# 150225_AriloRX_REV2_0_0.net
KiCad netlist of a schematic drawn in EAGLE
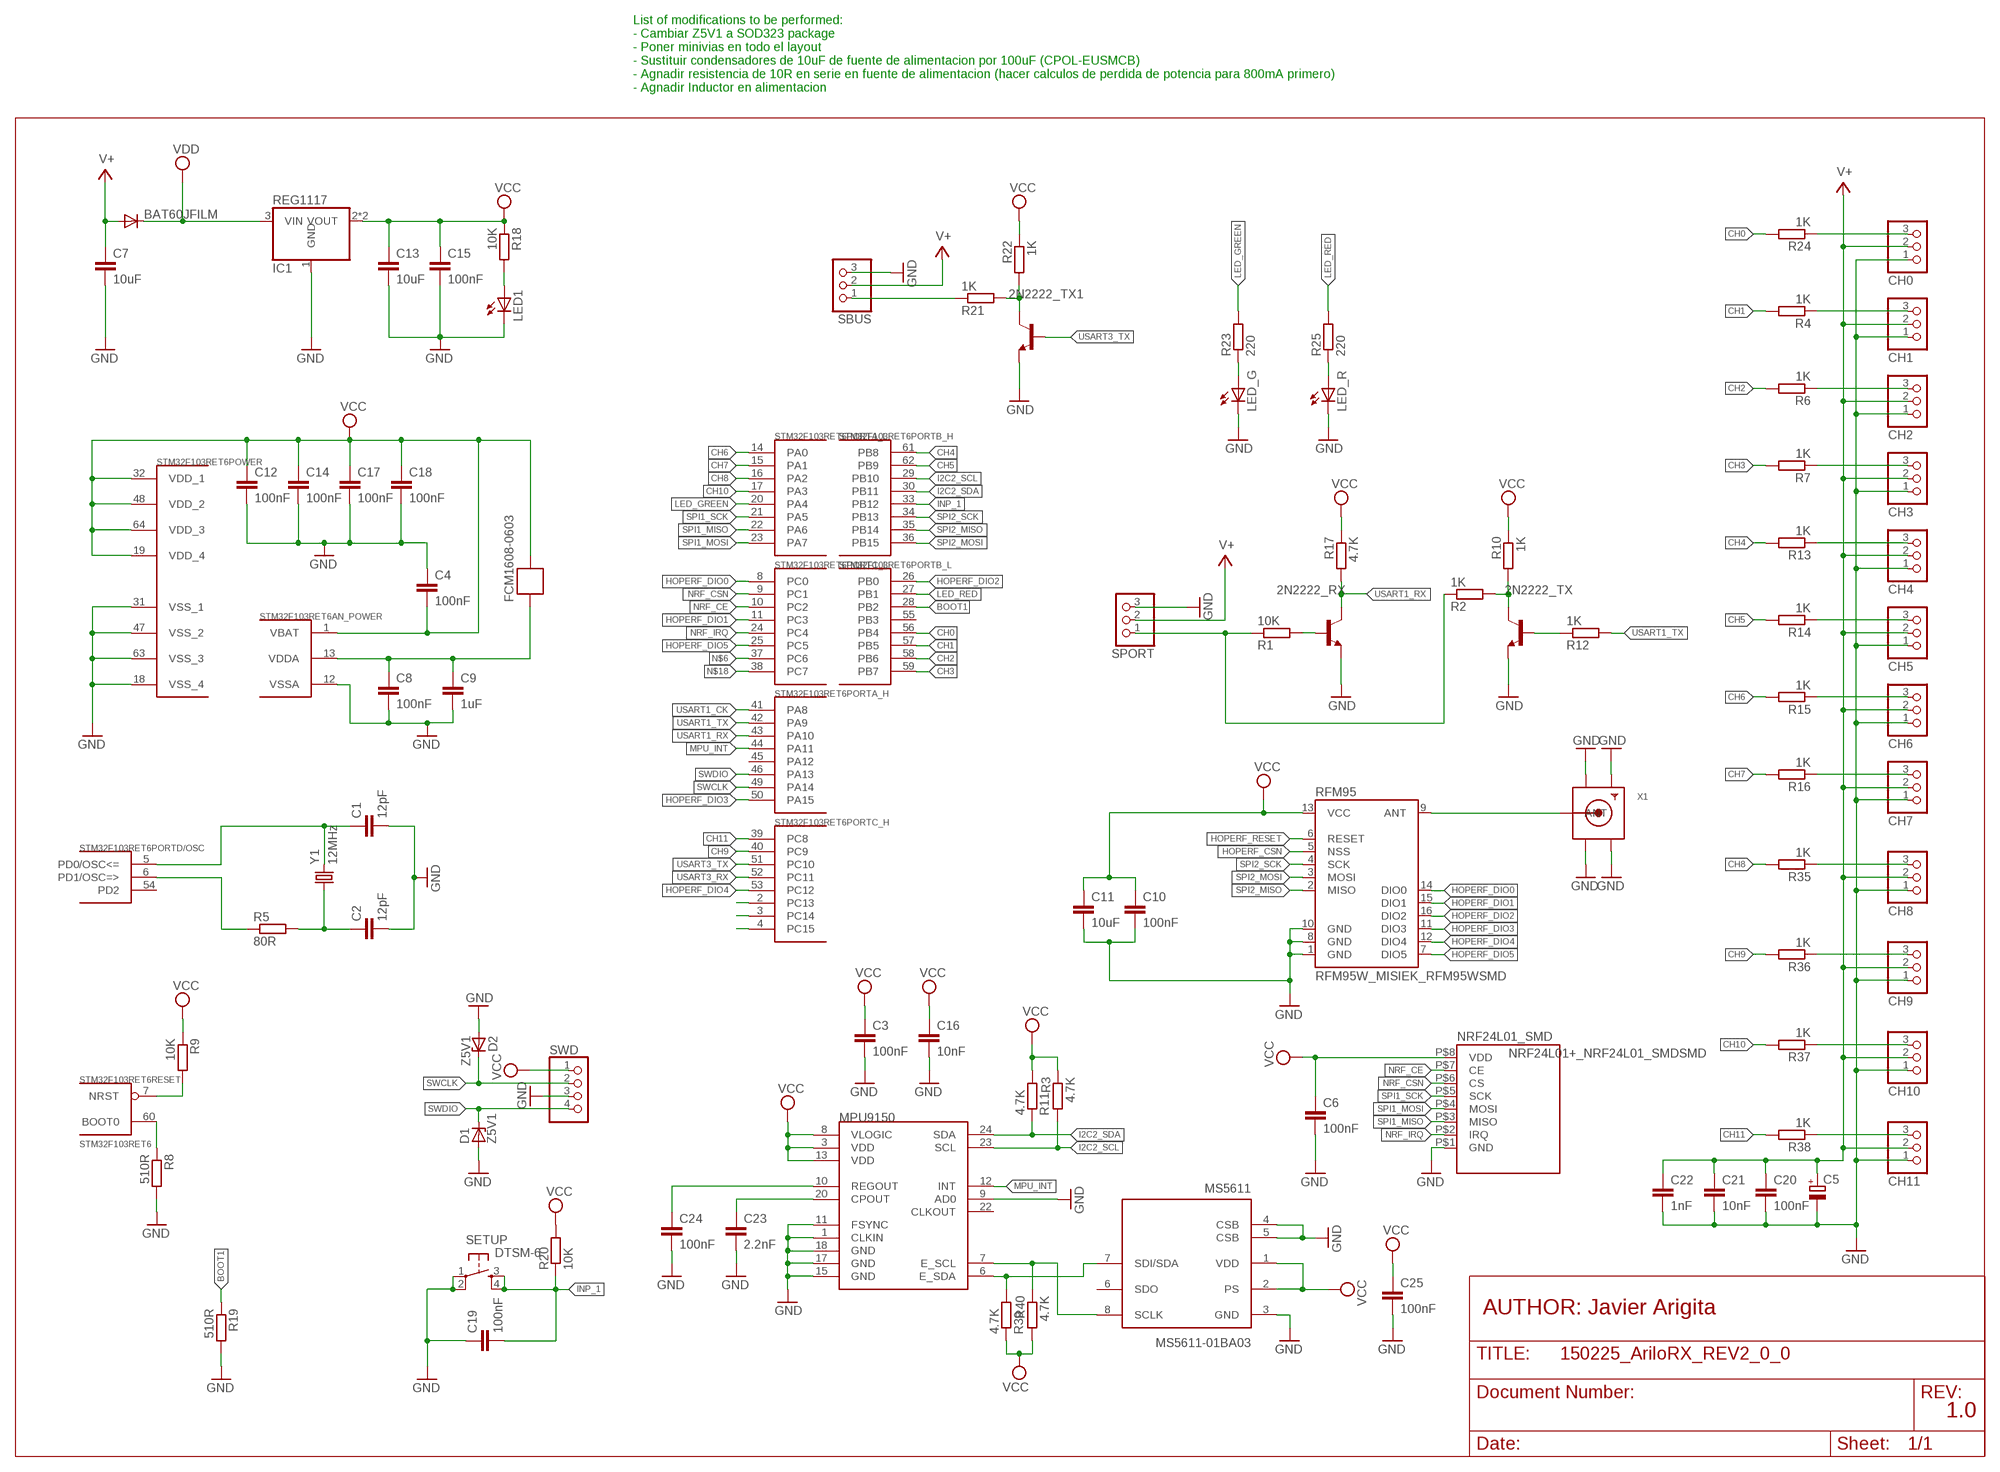
[diagram p0: schematic, sheet 1]

(export (version "E")
  (design (tool "Eeschema 10.0.6"))
  (components
    (comp (ref "2N2222_RX")
      (value "MMBT2222ALT1-NPN-SOT23-BEC")
      (footprint "eagle-import:SOT23-BEC")
      (libsource (lib "eagle-import") (part "-NPN-SOT23-BECMMBT2222ALT1"))
    )
    (comp (ref "2N2222_TX")
      (value "MMBT2222ALT1-NPN-SOT23-BEC")
      (footprint "eagle-import:SOT23-BEC")
      (libsource (lib "eagle-import") (part "-NPN-SOT23-BECMMBT2222ALT1"))
    )
    (comp (ref "2N2222_TX1")
      (value "MMBT2222ALT1-NPN-SOT23-BEC")
      (footprint "eagle-import:SOT23-BEC")
      (libsource (lib "eagle-import") (part "-NPN-SOT23-BECMMBT2222ALT1"))
    )
    (comp (ref "BAT60JFILM")
      (value "DIODE-SOD323-R")
      (footprint "eagle-import:SOD323-R")
      (libsource (lib "eagle-import") (part "DIODE-SOD323-R"))
    )
    (comp (ref "C1")
      (value "12pF")
      (footprint "eagle-import:RESISTOR_C0603")
      (libsource (lib "eagle-import") (part "RESISTOR_C-EUC0603"))
    )
    (comp (ref "C2")
      (value "12pF")
      (footprint "eagle-import:RESISTOR_C0603")
      (libsource (lib "eagle-import") (part "RESISTOR_C-EUC0603"))
    )
    (comp (ref "C3")
      (value "100nF")
      (footprint "eagle-import:RESISTOR_C0603")
      (libsource (lib "eagle-import") (part "RESISTOR_C-EUC0603"))
    )
    (comp (ref "C4")
      (value "100nF")
      (footprint "eagle-import:RESISTOR_C0603")
      (libsource (lib "eagle-import") (part "RESISTOR_C-EUC0603"))
    )
    (comp (ref "C5")
      (value "CPOL-EUSMCB")
      (footprint "eagle-import:SMC_B")
      (libsource (lib "eagle-import") (part "CPOL-EUSMCB"))
    )
    (comp (ref "C6")
      (value "100nF")
      (footprint "eagle-import:RESISTOR_C0603")
      (libsource (lib "eagle-import") (part "RESISTOR_C-EUC0603"))
    )
    (comp (ref "C7")
      (value "10uF")
      (footprint "eagle-import:RESISTOR_C3216")
      (libsource (lib "eagle-import") (part "RESISTOR_C-EUC3216"))
    )
    (comp (ref "C8")
      (value "100nF")
      (footprint "eagle-import:RESISTOR_C0603")
      (libsource (lib "eagle-import") (part "RESISTOR_C-EUC0603"))
    )
    (comp (ref "C9")
      (value "1uF")
      (footprint "eagle-import:RESISTOR_C0603")
      (libsource (lib "eagle-import") (part "RESISTOR_C-EUC0603"))
    )
    (comp (ref "C10")
      (value "100nF")
      (footprint "eagle-import:RESISTOR_C0603")
      (libsource (lib "eagle-import") (part "RESISTOR_C-EUC0603"))
    )
    (comp (ref "C11")
      (value "10uF")
      (footprint "eagle-import:RESISTOR_C3216")
      (libsource (lib "eagle-import") (part "RESISTOR_C-EUC3216"))
    )
    (comp (ref "C12")
      (value "100nF")
      (footprint "eagle-import:RESISTOR_C0603")
      (libsource (lib "eagle-import") (part "RESISTOR_C-EUC0603"))
    )
    (comp (ref "C13")
      (value "10uF")
      (footprint "eagle-import:RESISTOR_C3216")
      (libsource (lib "eagle-import") (part "RESISTOR_C-EUC3216"))
    )
    (comp (ref "C14")
      (value "100nF")
      (footprint "eagle-import:RESISTOR_C0603")
      (libsource (lib "eagle-import") (part "RESISTOR_C-EUC0603"))
    )
    (comp (ref "C15")
      (value "100nF")
      (footprint "eagle-import:RESISTOR_C0603")
      (libsource (lib "eagle-import") (part "RESISTOR_C-EUC0603"))
    )
    (comp (ref "C16")
      (value "10nF")
      (footprint "eagle-import:RESISTOR_C0603")
      (libsource (lib "eagle-import") (part "RESISTOR_C-EUC0603"))
    )
    (comp (ref "C17")
      (value "100nF")
      (footprint "eagle-import:RESISTOR_C0603")
      (libsource (lib "eagle-import") (part "RESISTOR_C-EUC0603"))
    )
    (comp (ref "C18")
      (value "100nF")
      (footprint "eagle-import:RESISTOR_C0603")
      (libsource (lib "eagle-import") (part "RESISTOR_C-EUC0603"))
    )
    (comp (ref "C19")
      (value "100nF")
      (footprint "eagle-import:RESISTOR_C0603")
      (libsource (lib "eagle-import") (part "RESISTOR_C-EUC0603"))
    )
    (comp (ref "C20")
      (value "100nF")
      (footprint "eagle-import:RESISTOR_C0603")
      (libsource (lib "eagle-import") (part "RESISTOR_C-EUC0603"))
    )
    (comp (ref "C21")
      (value "10nF")
      (footprint "eagle-import:RESISTOR_C0603")
      (libsource (lib "eagle-import") (part "RESISTOR_C-EUC0603"))
    )
    (comp (ref "C22")
      (value "1nF")
      (footprint "eagle-import:RESISTOR_C0603")
      (libsource (lib "eagle-import") (part "RESISTOR_C-EUC0603"))
    )
    (comp (ref "C23")
      (value "2.2nF")
      (footprint "eagle-import:RESISTOR_C0603")
      (libsource (lib "eagle-import") (part "RESISTOR_C-EUC0603"))
    )
    (comp (ref "C24")
      (value "100nF")
      (footprint "eagle-import:RESISTOR_C0603")
      (libsource (lib "eagle-import") (part "RESISTOR_C-EUC0603"))
    )
    (comp (ref "C25")
      (value "100nF")
      (footprint "eagle-import:RESISTOR_C0603")
      (libsource (lib "eagle-import") (part "RESISTOR_C-EUC0603"))
    )
    (comp (ref "CH0")
      (value "PINHD-1X3")
      (footprint "eagle-import:1X03")
      (libsource (lib "eagle-import") (part "PINHD-1X3"))
    )
    (comp (ref "CH1")
      (value "PINHD-1X3")
      (footprint "eagle-import:1X03")
      (libsource (lib "eagle-import") (part "PINHD-1X3"))
    )
    (comp (ref "CH2")
      (value "PINHD-1X3")
      (footprint "eagle-import:1X03")
      (libsource (lib "eagle-import") (part "PINHD-1X3"))
    )
    (comp (ref "CH3")
      (value "PINHD-1X3")
      (footprint "eagle-import:1X03")
      (libsource (lib "eagle-import") (part "PINHD-1X3"))
    )
    (comp (ref "CH4")
      (value "PINHD-1X3")
      (footprint "eagle-import:1X03")
      (libsource (lib "eagle-import") (part "PINHD-1X3"))
    )
    (comp (ref "CH5")
      (value "PINHD-1X3")
      (footprint "eagle-import:1X03")
      (libsource (lib "eagle-import") (part "PINHD-1X3"))
    )
    (comp (ref "CH6")
      (value "PINHD-1X3")
      (footprint "eagle-import:1X03")
      (libsource (lib "eagle-import") (part "PINHD-1X3"))
    )
    (comp (ref "CH7")
      (value "PINHD-1X3")
      (footprint "eagle-import:1X03")
      (libsource (lib "eagle-import") (part "PINHD-1X3"))
    )
    (comp (ref "CH8")
      (value "PINHD-1X3")
      (footprint "eagle-import:1X03")
      (libsource (lib "eagle-import") (part "PINHD-1X3"))
    )
    (comp (ref "CH9")
      (value "PINHD-1X3")
      (footprint "eagle-import:1X03")
      (libsource (lib "eagle-import") (part "PINHD-1X3"))
    )
    (comp (ref "CH10")
      (value "PINHD-1X3")
      (footprint "eagle-import:1X03")
      (libsource (lib "eagle-import") (part "PINHD-1X3"))
    )
    (comp (ref "CH11")
      (value "PINHD-1X3")
      (footprint "eagle-import:1X03")
      (libsource (lib "eagle-import") (part "PINHD-1X3"))
    )
    (comp (ref "D1")
      (value "Z5V1")
      (footprint "eagle-import:SOD80C")
      (libsource (lib "eagle-import") (part "ZENER-DIODESOD80C"))
    )
    (comp (ref "D2")
      (value "Z5V1")
      (footprint "eagle-import:SOD80C")
      (libsource (lib "eagle-import") (part "ZENER-DIODESOD80C"))
    )
    (comp (ref "FCM1608-0603")
      (value "FERRITE-BEAD")
      (footprint "eagle-import:R0603")
      (libsource (lib "eagle-import") (part "FERRITE-BEAD"))
    )
    (comp (ref "IC1")
      (value "REG1117")
      (footprint "eagle-import:SOT223")
      (libsource (lib "eagle-import") (part "REG1117"))
    )
    (comp (ref "LED1")
      (value "LED_LEDCHIP-LED0603")
      (footprint "eagle-import:LED_CHIP-LED0603")
      (libsource (lib "eagle-import") (part "LED_LEDCHIP-LED0603"))
    )
    (comp (ref "LED_G")
      (value "LEDCHIP-LED0603")
      (footprint "eagle-import:CHIP-LED0603")
      (libsource (lib "eagle-import") (part "LEDCHIP-LED0603"))
    )
    (comp (ref "LED_R")
      (value "LEDCHIP-LED0603")
      (footprint "eagle-import:CHIP-LED0603")
      (libsource (lib "eagle-import") (part "LEDCHIP-LED0603"))
    )
    (comp (ref "MPU9150")
      (value "MPU-9150QFN-24-NP")
      (footprint "eagle-import:QFN-24-NP")
      (libsource (lib "eagle-import") (part "MPU-9150QFN-24-NP"))
    )
    (comp (ref "MS5611")
      (value "MS5611-01BA03")
      (footprint "eagle-import:SON125P300X500X100-8N")
      (libsource (lib "eagle-import") (part "MS5611-01BA03"))
    )
    (comp (ref "NRF24L01_SMD")
      (value "NRF24L01+_NRF24L01_SMDSMD")
      (footprint "eagle-import:NRF24L01+_NRF24L01_SMD")
      (libsource (lib "eagle-import") (part "NRF24L01+_NRF24L01_SMDSMD"))
    )
    (comp (ref "R1")
      (value "10K")
      (footprint "eagle-import:RCL_R0603")
      (libsource (lib "eagle-import") (part "RCL_R-EU_R0603"))
    )
    (comp (ref "R2")
      (value "1K")
      (footprint "eagle-import:RCL_R0603")
      (libsource (lib "eagle-import") (part "RCL_R-EU_R0603"))
    )
    (comp (ref "R3")
      (value "4.7K")
      (footprint "eagle-import:RCL_R0603")
      (libsource (lib "eagle-import") (part "RCL_R-EU_R0603"))
    )
    (comp (ref "R4")
      (value "1K")
      (footprint "eagle-import:RCL_R0603")
      (libsource (lib "eagle-import") (part "RCL_R-EU_R0603"))
    )
    (comp (ref "R5")
      (value "80R")
      (footprint "eagle-import:RCL_R0603")
      (libsource (lib "eagle-import") (part "RCL_R-EU_R0603"))
    )
    (comp (ref "R6")
      (value "1K")
      (footprint "eagle-import:RCL_R0603")
      (libsource (lib "eagle-import") (part "RCL_R-EU_R0603"))
    )
    (comp (ref "R7")
      (value "1K")
      (footprint "eagle-import:RCL_R0603")
      (libsource (lib "eagle-import") (part "RCL_R-EU_R0603"))
    )
    (comp (ref "R8")
      (value "510R")
      (footprint "eagle-import:RCL_R0603")
      (libsource (lib "eagle-import") (part "RCL_R-EU_R0603"))
    )
    (comp (ref "R9")
      (value "10K")
      (footprint "eagle-import:RCL_R0603")
      (libsource (lib "eagle-import") (part "RCL_R-EU_R0603"))
    )
    (comp (ref "R10")
      (value "1K")
      (footprint "eagle-import:RCL_R0603")
      (libsource (lib "eagle-import") (part "RCL_R-EU_R0603"))
    )
    (comp (ref "R11")
      (value "4.7K")
      (footprint "eagle-import:RCL_R0603")
      (libsource (lib "eagle-import") (part "RCL_R-EU_R0603"))
    )
    (comp (ref "R12")
      (value "1K")
      (footprint "eagle-import:RCL_R0603")
      (libsource (lib "eagle-import") (part "RCL_R-EU_R0603"))
    )
    (comp (ref "R13")
      (value "1K")
      (footprint "eagle-import:RCL_R0603")
      (libsource (lib "eagle-import") (part "RCL_R-EU_R0603"))
    )
    (comp (ref "R14")
      (value "1K")
      (footprint "eagle-import:RCL_R0603")
      (libsource (lib "eagle-import") (part "RCL_R-EU_R0603"))
    )
    (comp (ref "R15")
      (value "1K")
      (footprint "eagle-import:RCL_R0603")
      (libsource (lib "eagle-import") (part "RCL_R-EU_R0603"))
    )
    (comp (ref "R16")
      (value "1K")
      (footprint "eagle-import:RCL_R0603")
      (libsource (lib "eagle-import") (part "RCL_R-EU_R0603"))
    )
    (comp (ref "R17")
      (value "4.7K")
      (footprint "eagle-import:RCL_R0603")
      (libsource (lib "eagle-import") (part "RCL_R-EU_R0603"))
    )
    (comp (ref "R18")
      (value "10K")
      (footprint "eagle-import:RCL_R0603")
      (libsource (lib "eagle-import") (part "RCL_R-EU_R0603"))
    )
    (comp (ref "R19")
      (value "510R")
      (footprint "eagle-import:RCL_R0603")
      (libsource (lib "eagle-import") (part "RCL_R-EU_R0603"))
    )
    (comp (ref "R20")
      (value "10K")
      (footprint "eagle-import:RCL_R0603")
      (libsource (lib "eagle-import") (part "RCL_R-EU_R0603"))
    )
    (comp (ref "R21")
      (value "1K")
      (footprint "eagle-import:RCL_R0603")
      (libsource (lib "eagle-import") (part "RCL_R-EU_R0603"))
    )
    (comp (ref "R22")
      (value "1K")
      (footprint "eagle-import:RCL_R0603")
      (libsource (lib "eagle-import") (part "RCL_R-EU_R0603"))
    )
    (comp (ref "R23")
      (value "220")
      (footprint "eagle-import:RCL_R0603")
      (libsource (lib "eagle-import") (part "RCL_R-EU_R0603"))
    )
    (comp (ref "R24")
      (value "1K")
      (footprint "eagle-import:RCL_R0603")
      (libsource (lib "eagle-import") (part "RCL_R-EU_R0603"))
    )
    (comp (ref "R25")
      (value "220")
      (footprint "eagle-import:RCL_R0603")
      (libsource (lib "eagle-import") (part "RCL_R-EU_R0603"))
    )
    (comp (ref "R35")
      (value "1K")
      (footprint "eagle-import:RCL_R0603")
      (libsource (lib "eagle-import") (part "RCL_R-EU_R0603"))
    )
    (comp (ref "R36")
      (value "1K")
      (footprint "eagle-import:RCL_R0603")
      (libsource (lib "eagle-import") (part "RCL_R-EU_R0603"))
    )
    (comp (ref "R37")
      (value "1K")
      (footprint "eagle-import:RCL_R0603")
      (libsource (lib "eagle-import") (part "RCL_R-EU_R0603"))
    )
    (comp (ref "R38")
      (value "1K")
      (footprint "eagle-import:RCL_R0603")
      (libsource (lib "eagle-import") (part "RCL_R-EU_R0603"))
    )
    (comp (ref "R39")
      (value "4.7K")
      (footprint "eagle-import:RCL_R0603")
      (libsource (lib "eagle-import") (part "RCL_R-EU_R0603"))
    )
    (comp (ref "R40")
      (value "4.7K")
      (footprint "eagle-import:RCL_R0603")
      (libsource (lib "eagle-import") (part "RCL_R-EU_R0603"))
    )
    (comp (ref "RFM95")
      (value "RFM95W_MISIEK_RFM95WSMD")
      (footprint "eagle-import:RFM95W_MISIEK_RFM95W_SMD")
      (libsource (lib "eagle-import") (part "RFM95W_MISIEK_RFM95WSMD"))
    )
    (comp (ref "SBUS")
      (value "PINHD-1X3")
      (footprint "eagle-import:1X03")
      (libsource (lib "eagle-import") (part "PINHD-1X3"))
    )
    (comp (ref "SETUP")
      (value "DTSM-6")
      (footprint "eagle-import:DTSM-6")
      (libsource (lib "eagle-import") (part "DTSM-6"))
    )
    (comp (ref "SPORT")
      (value "PINHD-1X3")
      (footprint "eagle-import:1X03")
      (libsource (lib "eagle-import") (part "PINHD-1X3"))
    )
    (comp (ref "STM32F103RET6")
      (value "STM32F103RET6")
      (footprint "eagle-import:TQFP64")
      (libsource (lib "eagle-import") (part "STM32F10XRXT6"))
    )
    (comp (ref "SWD")
      (value "PINHD-1X4")
      (footprint "eagle-import:1X04")
      (libsource (lib "eagle-import") (part "PINHD-1X4"))
    )
    (comp (ref "X1")
      (value "SMACONNECTOR_EDGE")
      (footprint "eagle-import:SMA_EDGELAUNCH")
      (libsource (lib "eagle-import") (part "SMACONNECTOR_EDGE"))
    )
    (comp (ref "Y1")
      (value "12MHz")
      (footprint "eagle-import:CRYSTAL-SMD-5X3")
      (libsource (lib "eagle-import") (part "CRYSTAL5X3"))
    )
  )
  (nets
    (net (code "1") (name "BOOT1") (class "Default")
      (node (ref "R19") (pin "1") (pinfunction "1_1") (pintype "passive"))
      (node (ref "STM32F103RET6") (pin "28") (pinfunction "PB2_28") (pintype "bidirectional"))
    )
    (net (code "2") (name "CH0") (class "Default")
      (node (ref "R24") (pin "2") (pinfunction "2_2") (pintype "passive"))
      (node (ref "STM32F103RET6") (pin "56") (pinfunction "PB4_56") (pintype "bidirectional"))
    )
    (net (code "3") (name "CH1") (class "Default")
      (node (ref "R4") (pin "2") (pinfunction "2_2") (pintype "passive"))
      (node (ref "STM32F103RET6") (pin "57") (pinfunction "PB5_57") (pintype "bidirectional"))
    )
    (net (code "4") (name "CH2") (class "Default")
      (node (ref "R6") (pin "2") (pinfunction "2_2") (pintype "passive"))
      (node (ref "STM32F103RET6") (pin "58") (pinfunction "PB6_58") (pintype "bidirectional"))
    )
    (net (code "5") (name "CH3") (class "Default")
      (node (ref "R7") (pin "2") (pinfunction "2_2") (pintype "passive"))
      (node (ref "STM32F103RET6") (pin "59") (pinfunction "PB7_59") (pintype "bidirectional"))
    )
    (net (code "6") (name "CH4") (class "Default")
      (node (ref "R13") (pin "2") (pinfunction "2_2") (pintype "passive"))
      (node (ref "STM32F103RET6") (pin "61") (pinfunction "PB8_61") (pintype "bidirectional"))
    )
    (net (code "7") (name "CH5") (class "Default")
      (node (ref "R14") (pin "2") (pinfunction "2_2") (pintype "passive"))
      (node (ref "STM32F103RET6") (pin "62") (pinfunction "PB9_62") (pintype "bidirectional"))
    )
    (net (code "8") (name "CH6") (class "Default")
      (node (ref "R15") (pin "2") (pinfunction "2_2") (pintype "passive"))
      (node (ref "STM32F103RET6") (pin "14") (pinfunction "PA0_14") (pintype "bidirectional"))
    )
    (net (code "9") (name "CH7") (class "Default")
      (node (ref "R16") (pin "2") (pinfunction "2_2") (pintype "passive"))
      (node (ref "STM32F103RET6") (pin "15") (pinfunction "PA1_15") (pintype "bidirectional"))
    )
    (net (code "10") (name "CH8") (class "Default")
      (node (ref "R35") (pin "2") (pinfunction "2_2") (pintype "passive"))
      (node (ref "STM32F103RET6") (pin "16") (pinfunction "PA2_16") (pintype "bidirectional"))
    )
    (net (code "11") (name "CH9") (class "Default")
      (node (ref "R36") (pin "2") (pinfunction "2_2") (pintype "passive"))
      (node (ref "STM32F103RET6") (pin "40") (pinfunction "PC9_40") (pintype "bidirectional"))
    )
    (net (code "12") (name "CH10") (class "Default")
      (node (ref "R37") (pin "2") (pinfunction "2_2") (pintype "passive"))
      (node (ref "STM32F103RET6") (pin "17") (pinfunction "PA3_17") (pintype "bidirectional"))
    )
    (net (code "13") (name "CH11") (class "Default")
      (node (ref "R38") (pin "2") (pinfunction "2_2") (pintype "passive"))
      (node (ref "STM32F103RET6") (pin "39") (pinfunction "PC8_39") (pintype "bidirectional"))
    )
    (net (code "14") (name "GND") (class "Default")
      (node (ref "2N2222_RX") (pin "E") (pinfunction "E_E") (pintype "passive"))
      (node (ref "2N2222_TX") (pin "E") (pinfunction "E_E") (pintype "passive"))
      (node (ref "2N2222_TX1") (pin "E") (pinfunction "E_E") (pintype "passive"))
      (node (ref "C1") (pin "2") (pinfunction "2_2") (pintype "passive"))
      (node (ref "C10") (pin "2") (pinfunction "2_2") (pintype "passive"))
      (node (ref "C11") (pin "2") (pinfunction "2_2") (pintype "passive"))
      (node (ref "C12") (pin "2") (pinfunction "2_2") (pintype "passive"))
      (node (ref "C13") (pin "2") (pinfunction "2_2") (pintype "passive"))
      (node (ref "C14") (pin "2") (pinfunction "2_2") (pintype "passive"))
      (node (ref "C15") (pin "2") (pinfunction "2_2") (pintype "passive"))
      (node (ref "C16") (pin "2") (pinfunction "2_2") (pintype "passive"))
      (node (ref "C17") (pin "2") (pinfunction "2_2") (pintype "passive"))
      (node (ref "C18") (pin "2") (pinfunction "2_2") (pintype "passive"))
      (node (ref "C19") (pin "1") (pinfunction "1_1") (pintype "passive"))
      (node (ref "C2") (pin "2") (pinfunction "2_2") (pintype "passive"))
      (node (ref "C20") (pin "2") (pinfunction "2_2") (pintype "passive"))
      (node (ref "C21") (pin "2") (pinfunction "2_2") (pintype "passive"))
      (node (ref "C22") (pin "2") (pinfunction "2_2") (pintype "passive"))
      (node (ref "C23") (pin "2") (pinfunction "2_2") (pintype "passive"))
      (node (ref "C24") (pin "2") (pinfunction "2_2") (pintype "passive"))
      (node (ref "C25") (pin "2") (pinfunction "2_2") (pintype "passive"))
      (node (ref "C3") (pin "2") (pinfunction "2_2") (pintype "passive"))
      (node (ref "C4") (pin "1") (pinfunction "1_1") (pintype "passive"))
      (node (ref "C5") (pin "-") (pinfunction "-_-") (pintype "passive"))
      (node (ref "C6") (pin "2") (pinfunction "2_2") (pintype "passive"))
      (node (ref "C7") (pin "2") (pinfunction "2_2") (pintype "passive"))
      (node (ref "C8") (pin "2") (pinfunction "2_2") (pintype "passive"))
      (node (ref "C9") (pin "2") (pinfunction "2_2") (pintype "passive"))
      (node (ref "CH0") (pin "1") (pinfunction "1_1") (pintype "passive"))
      (node (ref "CH1") (pin "1") (pinfunction "1_1") (pintype "passive"))
      (node (ref "CH10") (pin "1") (pinfunction "1_1") (pintype "passive"))
      (node (ref "CH11") (pin "1") (pinfunction "1_1") (pintype "passive"))
      (node (ref "CH2") (pin "1") (pinfunction "1_1") (pintype "passive"))
      (node (ref "CH3") (pin "1") (pinfunction "1_1") (pintype "passive"))
      (node (ref "CH4") (pin "1") (pinfunction "1_1") (pintype "passive"))
      (node (ref "CH5") (pin "1") (pinfunction "1_1") (pintype "passive"))
      (node (ref "CH6") (pin "1") (pinfunction "1_1") (pintype "passive"))
      (node (ref "CH7") (pin "1") (pinfunction "1_1") (pintype "passive"))
      (node (ref "CH8") (pin "1") (pinfunction "1_1") (pintype "passive"))
      (node (ref "CH9") (pin "1") (pinfunction "1_1") (pintype "passive"))
      (node (ref "D1") (pin "A") (pinfunction "A_A") (pintype "passive"))
      (node (ref "D2") (pin "A") (pinfunction "A_A") (pintype "passive"))
      (node (ref "IC1") (pin "1") (pinfunction "GND_1") (pintype "power_in"))
      (node (ref "LED1") (pin "C") (pinfunction "C_C") (pintype "passive"))
      (node (ref "LED_G") (pin "C") (pinfunction "C_C") (pintype "passive"))
      (node (ref "LED_R") (pin "C") (pinfunction "C_C") (pintype "passive"))
      (node (ref "MPU9150") (pin "1") (pinfunction "CLKIN_1") (pintype "bidirectional"))
      (node (ref "MPU9150") (pin "11") (pinfunction "FSYNC_11") (pintype "bidirectional"))
      (node (ref "MPU9150") (pin "15") (pinfunction "GND_15") (pintype "bidirectional"))
      (node (ref "MPU9150") (pin "17") (pinfunction "GND_17") (pintype "bidirectional"))
      (node (ref "MPU9150") (pin "18") (pinfunction "GND_18") (pintype "bidirectional"))
      (node (ref "MPU9150") (pin "9") (pinfunction "AD0_9") (pintype "bidirectional"))
      (node (ref "MS5611") (pin "3") (pinfunction "GND_3") (pintype "power_in"))
      (node (ref "MS5611") (pin "4") (pinfunction "CSB_4") (pintype "input"))
      (node (ref "MS5611") (pin "5") (pinfunction "CSB_5") (pintype "input"))
      (node (ref "NRF24L01_SMD") (pin "P$1") (pinfunction "GND_P$1") (pintype "power_in"))
      (node (ref "R19") (pin "2") (pinfunction "2_2") (pintype "passive"))
      (node (ref "R8") (pin "2") (pinfunction "2_2") (pintype "passive"))
      (node (ref "RFM95") (pin "1") (pinfunction "GND_1") (pintype "power_in"))
      (node (ref "RFM95") (pin "10") (pinfunction "GND_10") (pintype "power_in"))
      (node (ref "RFM95") (pin "8") (pinfunction "GND_8") (pintype "power_in"))
      (node (ref "SBUS") (pin "3") (pinfunction "3_3") (pintype "passive"))
      (node (ref "SETUP") (pin "1") (pinfunction "1_1") (pintype "passive"))
      (node (ref "SETUP") (pin "2") (pinfunction "2_2") (pintype "passive"))
      (node (ref "SPORT") (pin "3") (pinfunction "3_3") (pintype "passive"))
      (node (ref "STM32F103RET6") (pin "12") (pinfunction "VSSA_12") (pintype "power_in"))
      (node (ref "STM32F103RET6") (pin "18") (pinfunction "VSS_4_18") (pintype "power_in"))
      (node (ref "STM32F103RET6") (pin "31") (pinfunction "VSS_1_31") (pintype "power_in"))
      (node (ref "STM32F103RET6") (pin "47") (pinfunction "VSS_2_47") (pintype "power_in"))
      (node (ref "STM32F103RET6") (pin "63") (pinfunction "VSS_3_63") (pintype "power_in"))
      (node (ref "SWD") (pin "3") (pinfunction "3_3") (pintype "passive"))
      (node (ref "X1") (pin "GND@1") (pinfunction "GND4_GND@1") (pintype "power_in"))
      (node (ref "X1") (pin "GND@2") (pinfunction "GND3_GND@2") (pintype "power_in"))
      (node (ref "X1") (pin "GND@3") (pinfunction "GND2_GND@3") (pintype "power_in"))
      (node (ref "X1") (pin "GND@4") (pinfunction "GND1_GND@4") (pintype "power_in"))
    )
    (net (code "15") (name "HOPERF_CSN") (class "Default")
      (node (ref "RFM95") (pin "5") (pinfunction "NSS_5") (pintype "input"))
    )
    (net (code "16") (name "HOPERF_DIO0") (class "Default")
      (node (ref "RFM95") (pin "14") (pinfunction "DIO0_14") (pintype "input"))
      (node (ref "STM32F103RET6") (pin "8") (pinfunction "PC0_8") (pintype "bidirectional"))
    )
    (net (code "17") (name "HOPERF_DIO1") (class "Default")
      (node (ref "RFM95") (pin "15") (pinfunction "DIO1_15") (pintype "input"))
      (node (ref "STM32F103RET6") (pin "11") (pinfunction "PC3_11") (pintype "bidirectional"))
    )
    (net (code "18") (name "HOPERF_DIO2") (class "Default")
      (node (ref "RFM95") (pin "16") (pinfunction "DIO2_16") (pintype "input"))
      (node (ref "STM32F103RET6") (pin "26") (pinfunction "PB0_26") (pintype "bidirectional"))
    )
    (net (code "19") (name "HOPERF_DIO3") (class "Default")
      (node (ref "RFM95") (pin "11") (pinfunction "DIO3_11") (pintype "bidirectional"))
      (node (ref "STM32F103RET6") (pin "50") (pinfunction "PA15_50") (pintype "bidirectional"))
    )
    (net (code "20") (name "HOPERF_DIO4") (class "Default")
      (node (ref "RFM95") (pin "12") (pinfunction "DIO4_12") (pintype "bidirectional"))
      (node (ref "STM32F103RET6") (pin "53") (pinfunction "PC12_53") (pintype "bidirectional"))
    )
    (net (code "21") (name "HOPERF_DIO5") (class "Default")
      (node (ref "RFM95") (pin "7") (pinfunction "DIO5_7") (pintype "bidirectional"))
      (node (ref "STM32F103RET6") (pin "25") (pinfunction "PC5_25") (pintype "bidirectional"))
    )
    (net (code "22") (name "HOPERF_RESET") (class "Default")
      (node (ref "RFM95") (pin "6") (pinfunction "RESET_6") (pintype "output"))
    )
    (net (code "23") (name "I2C2_SCL") (class "Default")
      (node (ref "MPU9150") (pin "23") (pinfunction "SCL_23") (pintype "bidirectional"))
      (node (ref "R3") (pin "2") (pinfunction "2_2") (pintype "passive"))
      (node (ref "STM32F103RET6") (pin "29") (pinfunction "PB10_29") (pintype "bidirectional"))
    )
    (net (code "24") (name "I2C2_SDA") (class "Default")
      (node (ref "MPU9150") (pin "24") (pinfunction "SDA_24") (pintype "bidirectional"))
      (node (ref "R11") (pin "1") (pinfunction "1_1") (pintype "passive"))
      (node (ref "STM32F103RET6") (pin "30") (pinfunction "PB11_30") (pintype "bidirectional"))
    )
    (net (code "25") (name "INP_1") (class "Default")
      (node (ref "C19") (pin "2") (pinfunction "2_2") (pintype "passive"))
      (node (ref "R20") (pin "1") (pinfunction "1_1") (pintype "passive"))
      (node (ref "SETUP") (pin "3") (pinfunction "3_3") (pintype "passive"))
      (node (ref "SETUP") (pin "4") (pinfunction "4_4") (pintype "passive"))
      (node (ref "STM32F103RET6") (pin "33") (pinfunction "PB12_33") (pintype "bidirectional"))
    )
    (net (code "26") (name "LED_GREEN") (class "Default")
      (node (ref "R23") (pin "2") (pinfunction "2_2") (pintype "passive"))
      (node (ref "STM32F103RET6") (pin "20") (pinfunction "PA4_20") (pintype "bidirectional"))
    )
    (net (code "27") (name "LED_RED") (class "Default")
      (node (ref "R25") (pin "2") (pinfunction "2_2") (pintype "passive"))
      (node (ref "STM32F103RET6") (pin "27") (pinfunction "PB1_27") (pintype "bidirectional"))
    )
    (net (code "28") (name "MPU_INT") (class "Default")
      (node (ref "MPU9150") (pin "12") (pinfunction "INT_12") (pintype "bidirectional"))
      (node (ref "STM32F103RET6") (pin "44") (pinfunction "PA11_44") (pintype "bidirectional"))
    )
    (net (code "29") (name "N$6") (class "Default")
      (node (ref "STM32F103RET6") (pin "37") (pinfunction "PC6_37") (pintype "bidirectional"))
    )
    (net (code "30") (name "N$18") (class "Default")
      (node (ref "STM32F103RET6") (pin "38") (pinfunction "PC7_38") (pintype "bidirectional"))
    )
    (net (code "31") (name "NRF_CE") (class "Default")
      (node (ref "NRF24L01_SMD") (pin "P$7") (pinfunction "CE_P$7") (pintype "input"))
      (node (ref "STM32F103RET6") (pin "10") (pinfunction "PC2_10") (pintype "bidirectional"))
    )
    (net (code "32") (name "NRF_CSN") (class "Default")
      (node (ref "NRF24L01_SMD") (pin "P$6") (pinfunction "CS_P$6") (pintype "input"))
      (node (ref "STM32F103RET6") (pin "9") (pinfunction "PC1_9") (pintype "bidirectional"))
    )
    (net (code "33") (name "NRF_IRQ") (class "Default")
      (node (ref "NRF24L01_SMD") (pin "P$2") (pinfunction "IRQ_P$2") (pintype "output"))
      (node (ref "STM32F103RET6") (pin "24") (pinfunction "PC4_24") (pintype "bidirectional"))
    )
    (net (code "34") (name "Net-(2N2222_RX-PadB)") (class "Default")
      (node (ref "2N2222_RX") (pin "B") (pinfunction "B_B") (pintype "passive"))
      (node (ref "R1") (pin "2") (pinfunction "2_2") (pintype "passive"))
    )
    (net (code "35") (name "Net-(2N2222_TX-PadB)") (class "Default")
      (node (ref "2N2222_TX") (pin "B") (pinfunction "B_B") (pintype "passive"))
      (node (ref "R12") (pin "1") (pinfunction "1_1") (pintype "passive"))
    )
    (net (code "36") (name "Net-(2N2222_TX-PadC)") (class "Default")
      (node (ref "2N2222_TX") (pin "C") (pinfunction "C_C") (pintype "passive"))
      (node (ref "R10") (pin "2") (pinfunction "2_2") (pintype "passive"))
      (node (ref "R2") (pin "2") (pinfunction "2_2") (pintype "passive"))
    )
    (net (code "37") (name "Net-(2N2222_TX1-PadC)") (class "Default")
      (node (ref "2N2222_TX1") (pin "C") (pinfunction "C_C") (pintype "passive"))
      (node (ref "R21") (pin "2") (pinfunction "2_2") (pintype "passive"))
      (node (ref "R22") (pin "2") (pinfunction "2_2") (pintype "passive"))
    )
    (net (code "38") (name "Net-(C2-Pad1)") (class "Default")
      (node (ref "C2") (pin "1") (pinfunction "1_1") (pintype "passive"))
      (node (ref "R5") (pin "2") (pinfunction "2_2") (pintype "passive"))
      (node (ref "Y1") (pin "1") (pinfunction "1_1") (pintype "passive"))
    )
    (net (code "39") (name "Net-(CH0-Pad3)") (class "Default")
      (node (ref "CH0") (pin "3") (pinfunction "3_3") (pintype "passive"))
      (node (ref "R24") (pin "1") (pinfunction "1_1") (pintype "passive"))
    )
    (net (code "40") (name "Net-(CH1-Pad3)") (class "Default")
      (node (ref "CH1") (pin "3") (pinfunction "3_3") (pintype "passive"))
      (node (ref "R4") (pin "1") (pinfunction "1_1") (pintype "passive"))
    )
    (net (code "41") (name "Net-(CH2-Pad3)") (class "Default")
      (node (ref "CH2") (pin "3") (pinfunction "3_3") (pintype "passive"))
      (node (ref "R6") (pin "1") (pinfunction "1_1") (pintype "passive"))
    )
    (net (code "42") (name "Net-(CH3-Pad3)") (class "Default")
      (node (ref "CH3") (pin "3") (pinfunction "3_3") (pintype "passive"))
      (node (ref "R7") (pin "1") (pinfunction "1_1") (pintype "passive"))
    )
    (net (code "43") (name "Net-(CH4-Pad3)") (class "Default")
      (node (ref "CH4") (pin "3") (pinfunction "3_3") (pintype "passive"))
      (node (ref "R13") (pin "1") (pinfunction "1_1") (pintype "passive"))
    )
    (net (code "44") (name "Net-(CH5-Pad3)") (class "Default")
      (node (ref "CH5") (pin "3") (pinfunction "3_3") (pintype "passive"))
      (node (ref "R14") (pin "1") (pinfunction "1_1") (pintype "passive"))
    )
    (net (code "45") (name "Net-(CH6-Pad3)") (class "Default")
      (node (ref "CH6") (pin "3") (pinfunction "3_3") (pintype "passive"))
      (node (ref "R15") (pin "1") (pinfunction "1_1") (pintype "passive"))
    )
    (net (code "46") (name "Net-(CH7-Pad3)") (class "Default")
      (node (ref "CH7") (pin "3") (pinfunction "3_3") (pintype "passive"))
      (node (ref "R16") (pin "1") (pinfunction "1_1") (pintype "passive"))
    )
    (net (code "47") (name "Net-(CH8-Pad3)") (class "Default")
      (node (ref "CH8") (pin "3") (pinfunction "3_3") (pintype "passive"))
      (node (ref "R35") (pin "1") (pinfunction "1_1") (pintype "passive"))
    )
    (net (code "48") (name "Net-(CH9-Pad3)") (class "Default")
      (node (ref "CH9") (pin "3") (pinfunction "3_3") (pintype "passive"))
      (node (ref "R36") (pin "1") (pinfunction "1_1") (pintype "passive"))
    )
    (net (code "49") (name "Net-(CH10-Pad3)") (class "Default")
      (node (ref "CH10") (pin "3") (pinfunction "3_3") (pintype "passive"))
      (node (ref "R37") (pin "1") (pinfunction "1_1") (pintype "passive"))
    )
    (net (code "50") (name "Net-(CH11-Pad3)") (class "Default")
      (node (ref "CH11") (pin "3") (pinfunction "3_3") (pintype "passive"))
      (node (ref "R38") (pin "1") (pinfunction "1_1") (pintype "passive"))
    )
    (net (code "51") (name "Net-(FCM1608-0603-P$2)") (class "Default")
      (node (ref "C8") (pin "1") (pinfunction "1_1") (pintype "passive"))
      (node (ref "C9") (pin "1") (pinfunction "1_1") (pintype "passive"))
      (node (ref "FCM1608-0603") (pin "2") (pinfunction "P$2_2") (pintype "bidirectional"))
      (node (ref "STM32F103RET6") (pin "13") (pinfunction "VDDA_13") (pintype "power_in"))
    )
    (net (code "52") (name "Net-(LED1-PadA)") (class "Default")
      (node (ref "LED1") (pin "A") (pinfunction "A_A") (pintype "passive"))
      (node (ref "R18") (pin "2") (pinfunction "2_2") (pintype "passive"))
    )
    (net (code "53") (name "Net-(LED_G-PadA)") (class "Default")
      (node (ref "LED_G") (pin "A") (pinfunction "A_A") (pintype "passive"))
      (node (ref "R23") (pin "1") (pinfunction "1_1") (pintype "passive"))
    )
    (net (code "54") (name "Net-(LED_R-PadA)") (class "Default")
      (node (ref "LED_R") (pin "A") (pinfunction "A_A") (pintype "passive"))
      (node (ref "R25") (pin "1") (pinfunction "1_1") (pintype "passive"))
    )
    (net (code "55") (name "Net-(MPU9150-CPOUT)") (class "Default")
      (node (ref "C23") (pin "1") (pinfunction "1_1") (pintype "passive"))
      (node (ref "MPU9150") (pin "20") (pinfunction "CPOUT_20") (pintype "bidirectional"))
    )
    (net (code "56") (name "Net-(MPU9150-E_SCL)") (class "Default")
      (node (ref "MPU9150") (pin "7") (pinfunction "E_SCL_7") (pintype "bidirectional"))
      (node (ref "MS5611") (pin "8") (pinfunction "SCLK_8") (pintype "input"))
      (node (ref "R40") (pin "1") (pinfunction "1_1") (pintype "passive"))
    )
    (net (code "57") (name "Net-(MPU9150-E_SDA)") (class "Default")
      (node (ref "MPU9150") (pin "6") (pinfunction "E_SDA_6") (pintype "bidirectional"))
      (node (ref "MS5611") (pin "7") (pinfunction "SDI/SDA_7") (pintype "bidirectional"))
      (node (ref "R39") (pin "2") (pinfunction "2_2") (pintype "passive"))
    )
    (net (code "58") (name "Net-(MPU9150-REGOUT)") (class "Default")
      (node (ref "C24") (pin "1") (pinfunction "1_1") (pintype "passive"))
      (node (ref "MPU9150") (pin "10") (pinfunction "REGOUT_10") (pintype "bidirectional"))
    )
    (net (code "59") (name "Net-(R1-Pad1)") (class "Default")
      (node (ref "R1") (pin "1") (pinfunction "1_1") (pintype "passive"))
      (node (ref "R2") (pin "1") (pinfunction "1_1") (pintype "passive"))
      (node (ref "SPORT") (pin "1") (pinfunction "1_1") (pintype "passive"))
    )
    (net (code "60") (name "Net-(R21-Pad1)") (class "Default")
      (node (ref "R21") (pin "1") (pinfunction "1_1") (pintype "passive"))
      (node (ref "SBUS") (pin "1") (pinfunction "1_1") (pintype "passive"))
    )
    (net (code "61") (name "Net-(RFM95-ANT)") (class "Default")
      (node (ref "RFM95") (pin "9") (pinfunction "ANT_9") (pintype "bidirectional"))
      (node (ref "X1") (pin "P") (pinfunction "ANT_P") (pintype "bidirectional"))
    )
    (net (code "62") (name "Net-(STM32F103RET6H-PD0{slash}OSC<=)") (class "Default")
      (node (ref "C1") (pin "1") (pinfunction "1_1") (pintype "passive"))
      (node (ref "STM32F103RET6") (pin "5") (pinfunction "PD0/OSC<=_5") (pintype "bidirectional"))
      (node (ref "Y1") (pin "3") (pinfunction "2_3") (pintype "passive"))
    )
    (net (code "63") (name "Net-(STM32F103RET6H-PD1{slash}OSC=>)") (class "Default")
      (node (ref "R5") (pin "1") (pinfunction "1_1") (pintype "passive"))
      (node (ref "STM32F103RET6") (pin "6") (pinfunction "PD1/OSC=>_6") (pintype "bidirectional"))
    )
    (net (code "64") (name "Net-(STM32F103RET6J-BOOT0)") (class "Default")
      (node (ref "R8") (pin "1") (pinfunction "1_1") (pintype "passive"))
      (node (ref "STM32F103RET6") (pin "60") (pinfunction "BOOT0_60") (pintype "input"))
    )
    (net (code "65") (name "Net-(STM32F103RET6J-NRST)") (class "Default")
      (node (ref "R9") (pin "2") (pinfunction "2_2") (pintype "passive"))
      (node (ref "STM32F103RET6") (pin "7") (pinfunction "NRST_7") (pintype "input"))
    )
    (net (code "66") (name "SPI1_MISO") (class "Default")
      (node (ref "NRF24L01_SMD") (pin "P$3") (pinfunction "MISO_P$3") (pintype "output"))
      (node (ref "STM32F103RET6") (pin "22") (pinfunction "PA6_22") (pintype "bidirectional"))
    )
    (net (code "67") (name "SPI1_MOSI") (class "Default")
      (node (ref "NRF24L01_SMD") (pin "P$4") (pinfunction "MOSI_P$4") (pintype "input"))
      (node (ref "STM32F103RET6") (pin "23") (pinfunction "PA7_23") (pintype "bidirectional"))
    )
    (net (code "68") (name "SPI1_SCK") (class "Default")
      (node (ref "NRF24L01_SMD") (pin "P$5") (pinfunction "SCK_P$5") (pintype "input"))
      (node (ref "STM32F103RET6") (pin "21") (pinfunction "PA5_21") (pintype "bidirectional"))
    )
    (net (code "69") (name "SPI2_MISO") (class "Default")
      (node (ref "RFM95") (pin "2") (pinfunction "MISO_2") (pintype "output"))
      (node (ref "STM32F103RET6") (pin "35") (pinfunction "PB14_35") (pintype "bidirectional"))
    )
    (net (code "70") (name "SPI2_MOSI") (class "Default")
      (node (ref "RFM95") (pin "3") (pinfunction "MOSI_3") (pintype "input"))
      (node (ref "STM32F103RET6") (pin "36") (pinfunction "PB15_36") (pintype "bidirectional"))
    )
    (net (code "71") (name "SPI2_SCK") (class "Default")
      (node (ref "RFM95") (pin "4") (pinfunction "SCK_4") (pintype "input"))
      (node (ref "STM32F103RET6") (pin "34") (pinfunction "PB13_34") (pintype "bidirectional"))
    )
    (net (code "72") (name "SWCLK") (class "Default")
      (node (ref "D2") (pin "C") (pinfunction "C_C") (pintype "passive"))
      (node (ref "STM32F103RET6") (pin "49") (pinfunction "PA14_49") (pintype "bidirectional"))
      (node (ref "SWD") (pin "2") (pinfunction "2_2") (pintype "passive"))
    )
    (net (code "73") (name "SWDIO") (class "Default")
      (node (ref "D1") (pin "C") (pinfunction "C_C") (pintype "passive"))
      (node (ref "STM32F103RET6") (pin "46") (pinfunction "PA13_46") (pintype "bidirectional"))
      (node (ref "SWD") (pin "4") (pinfunction "4_4") (pintype "passive"))
    )
    (net (code "74") (name "USART1_CK") (class "Default")
      (node (ref "STM32F103RET6") (pin "41") (pinfunction "PA8_41") (pintype "bidirectional"))
    )
    (net (code "75") (name "USART1_RX") (class "Default")
      (node (ref "2N2222_RX") (pin "C") (pinfunction "C_C") (pintype "passive"))
      (node (ref "R17") (pin "2") (pinfunction "2_2") (pintype "passive"))
      (node (ref "STM32F103RET6") (pin "43") (pinfunction "PA10_43") (pintype "bidirectional"))
    )
    (net (code "76") (name "USART1_TX") (class "Default")
      (node (ref "R12") (pin "2") (pinfunction "2_2") (pintype "passive"))
      (node (ref "STM32F103RET6") (pin "42") (pinfunction "PA9_42") (pintype "bidirectional"))
    )
    (net (code "77") (name "USART3_RX") (class "Default")
      (node (ref "STM32F103RET6") (pin "52") (pinfunction "PC11_52") (pintype "bidirectional"))
    )
    (net (code "78") (name "USART3_TX") (class "Default")
      (node (ref "2N2222_TX1") (pin "B") (pinfunction "B_B") (pintype "passive"))
      (node (ref "STM32F103RET6") (pin "51") (pinfunction "PC10_51") (pintype "bidirectional"))
    )
    (net (code "79") (name "V+") (class "Default")
      (node (ref "BAT60JFILM") (pin "A") (pinfunction "A_A") (pintype "passive"))
      (node (ref "C20") (pin "1") (pinfunction "1_1") (pintype "passive"))
      (node (ref "C21") (pin "1") (pinfunction "1_1") (pintype "passive"))
      (node (ref "C22") (pin "1") (pinfunction "1_1") (pintype "passive"))
      (node (ref "C5") (pin "+") (pinfunction "+_+") (pintype "passive"))
      (node (ref "C7") (pin "1") (pinfunction "1_1") (pintype "passive"))
      (node (ref "CH0") (pin "2") (pinfunction "2_2") (pintype "passive"))
      (node (ref "CH1") (pin "2") (pinfunction "2_2") (pintype "passive"))
      (node (ref "CH10") (pin "2") (pinfunction "2_2") (pintype "passive"))
      (node (ref "CH11") (pin "2") (pinfunction "2_2") (pintype "passive"))
      (node (ref "CH2") (pin "2") (pinfunction "2_2") (pintype "passive"))
      (node (ref "CH3") (pin "2") (pinfunction "2_2") (pintype "passive"))
      (node (ref "CH4") (pin "2") (pinfunction "2_2") (pintype "passive"))
      (node (ref "CH5") (pin "2") (pinfunction "2_2") (pintype "passive"))
      (node (ref "CH6") (pin "2") (pinfunction "2_2") (pintype "passive"))
      (node (ref "CH7") (pin "2") (pinfunction "2_2") (pintype "passive"))
      (node (ref "CH8") (pin "2") (pinfunction "2_2") (pintype "passive"))
      (node (ref "CH9") (pin "2") (pinfunction "2_2") (pintype "passive"))
      (node (ref "SBUS") (pin "2") (pinfunction "2_2") (pintype "passive"))
      (node (ref "SPORT") (pin "2") (pinfunction "2_2") (pintype "passive"))
    )
    (net (code "80") (name "VCC") (class "Default")
      (node (ref "C10") (pin "1") (pinfunction "1_1") (pintype "passive"))
      (node (ref "C11") (pin "1") (pinfunction "1_1") (pintype "passive"))
      (node (ref "C12") (pin "1") (pinfunction "1_1") (pintype "passive"))
      (node (ref "C13") (pin "1") (pinfunction "1_1") (pintype "passive"))
      (node (ref "C14") (pin "1") (pinfunction "1_1") (pintype "passive"))
      (node (ref "C15") (pin "1") (pinfunction "1_1") (pintype "passive"))
      (node (ref "C16") (pin "1") (pinfunction "1_1") (pintype "passive"))
      (node (ref "C17") (pin "1") (pinfunction "1_1") (pintype "passive"))
      (node (ref "C18") (pin "1") (pinfunction "1_1") (pintype "passive"))
      (node (ref "C25") (pin "1") (pinfunction "1_1") (pintype "passive"))
      (node (ref "C3") (pin "1") (pinfunction "1_1") (pintype "passive"))
      (node (ref "C4") (pin "2") (pinfunction "2_2") (pintype "passive"))
      (node (ref "C6") (pin "1") (pinfunction "1_1") (pintype "passive"))
      (node (ref "FCM1608-0603") (pin "1") (pinfunction "P$1_1") (pintype "bidirectional"))
      (node (ref "IC1") (pin "2") (pinfunction "VOUT_2") (pintype "power_in"))
      (node (ref "IC1") (pin "4") (pinfunction "VOUT_4") (pintype "power_in"))
      (node (ref "MPU9150") (pin "13") (pinfunction "VDD_13") (pintype "bidirectional"))
      (node (ref "MPU9150") (pin "3") (pinfunction "VDD_3") (pintype "bidirectional"))
      (node (ref "MPU9150") (pin "8") (pinfunction "VLOGIC_8") (pintype "bidirectional"))
      (node (ref "MS5611") (pin "1") (pinfunction "VDD_1") (pintype "power_in"))
      (node (ref "MS5611") (pin "2") (pinfunction "PS_2") (pintype "input"))
      (node (ref "NRF24L01_SMD") (pin "P$8") (pinfunction "VDD_P$8") (pintype "bidirectional"))
      (node (ref "R10") (pin "1") (pinfunction "1_1") (pintype "passive"))
      (node (ref "R11") (pin "2") (pinfunction "2_2") (pintype "passive"))
      (node (ref "R17") (pin "1") (pinfunction "1_1") (pintype "passive"))
      (node (ref "R18") (pin "1") (pinfunction "1_1") (pintype "passive"))
      (node (ref "R20") (pin "2") (pinfunction "2_2") (pintype "passive"))
      (node (ref "R22") (pin "1") (pinfunction "1_1") (pintype "passive"))
      (node (ref "R3") (pin "1") (pinfunction "1_1") (pintype "passive"))
      (node (ref "R39") (pin "1") (pinfunction "1_1") (pintype "passive"))
      (node (ref "R40") (pin "2") (pinfunction "2_2") (pintype "passive"))
      (node (ref "R9") (pin "1") (pinfunction "1_1") (pintype "passive"))
      (node (ref "RFM95") (pin "13") (pinfunction "VCC_13") (pintype "bidirectional"))
      (node (ref "STM32F103RET6") (pin "1") (pinfunction "VBAT_1") (pintype "power_in"))
      (node (ref "STM32F103RET6") (pin "19") (pinfunction "VDD_4_19") (pintype "power_in"))
      (node (ref "STM32F103RET6") (pin "32") (pinfunction "VDD_1_32") (pintype "power_in"))
      (node (ref "STM32F103RET6") (pin "48") (pinfunction "VDD_2_48") (pintype "power_in"))
      (node (ref "STM32F103RET6") (pin "64") (pinfunction "VDD_3_64") (pintype "power_in"))
      (node (ref "SWD") (pin "1") (pinfunction "1_1") (pintype "passive"))
    )
    (net (code "81") (name "VDD") (class "Default")
      (node (ref "BAT60JFILM") (pin "C") (pinfunction "C_C") (pintype "passive"))
      (node (ref "IC1") (pin "3") (pinfunction "VIN_3") (pintype "input"))
    )
    (net (code "82") (name "unconnected-(MPU9150-CLKOUT-Pad22)") (class "Default")
      (node (ref "MPU9150") (pin "22") (pinfunction "CLKOUT_22") (pintype "bidirectional"))
    )
    (net (code "83") (name "unconnected-(MS5611-SDO-Pad6)") (class "Default")
      (node (ref "MS5611") (pin "6") (pinfunction "SDO_6") (pintype "output"))
    )
    (net (code "84") (name "unconnected-(STM32F103RET6B-PA12-Pad45)") (class "Default")
      (node (ref "STM32F103RET6") (pin "45") (pinfunction "PA12_45") (pintype "bidirectional"))
    )
    (net (code "85") (name "unconnected-(STM32F103RET6E-PB3-Pad55)") (class "Default")
      (node (ref "STM32F103RET6") (pin "55") (pinfunction "PB3_55") (pintype "bidirectional"))
    )
    (net (code "86") (name "unconnected-(STM32F103RET6F-PC13-Pad2)") (class "Default")
      (node (ref "STM32F103RET6") (pin "2") (pinfunction "PC13_2") (pintype "bidirectional"))
    )
    (net (code "87") (name "unconnected-(STM32F103RET6F-PC14-Pad3)") (class "Default")
      (node (ref "STM32F103RET6") (pin "3") (pinfunction "PC14_3") (pintype "bidirectional"))
    )
    (net (code "88") (name "unconnected-(STM32F103RET6F-PC15-Pad4)") (class "Default")
      (node (ref "STM32F103RET6") (pin "4") (pinfunction "PC15_4") (pintype "bidirectional"))
    )
    (net (code "89") (name "unconnected-(STM32F103RET6H-PD2-Pad54)") (class "Default")
      (node (ref "STM32F103RET6") (pin "54") (pinfunction "PD2_54") (pintype "bidirectional"))
    )
  )
)
